# MB_ZBT_memory.net
KiCad netlist of a schematic drawn in Altium Designer
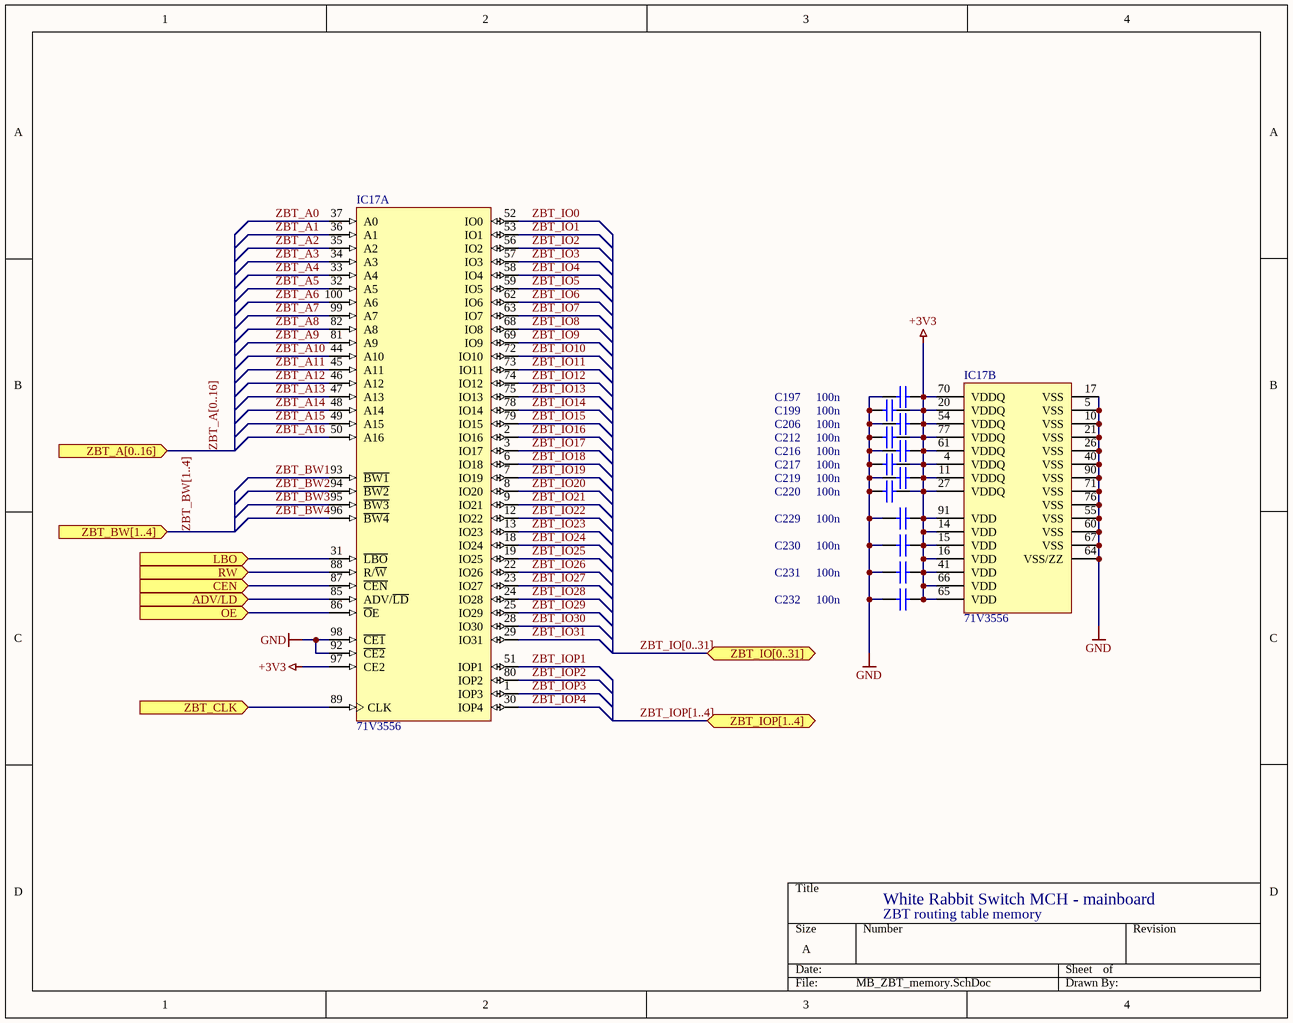
[diagram p0: MB_ZBT_memory.SchDoc]

(export (version "E")
  (design (tool "Eeschema 10.0.6"))
  (components
    (comp (ref "C197")
      (value "100n")
      (footprint "CAPC1005X55N")
      (description "Non-polarised capacitor")
      (fields
        (field (name "PART NUMBER") "CC0402_100NF_16V_10%_X7R")
        (field (name "VOLTAGE") "16V")
        (field (name "AUTHOR") "CERN DEM JLC")
      )
      (libsource (lib "Capacitors") (part "Capacitor - non polarized"))
    )
    (comp (ref "C199")
      (value "100n")
      (footprint "CAPC1005X55N")
      (description "Non-polarised capacitor")
      (fields
        (field (name "PART NUMBER") "CC0402_100NF_16V_10%_X7R")
        (field (name "VOLTAGE") "16V")
        (field (name "AUTHOR") "CERN DEM JLC")
      )
      (libsource (lib "Capacitors") (part "Capacitor - non polarized"))
    )
    (comp (ref "C206")
      (value "100n")
      (footprint "CAPC1005X55N")
      (description "Non-polarised capacitor")
      (fields
        (field (name "PART NUMBER") "CC0402_100NF_16V_10%_X7R")
        (field (name "VOLTAGE") "16V")
        (field (name "AUTHOR") "CERN DEM JLC")
      )
      (libsource (lib "Capacitors") (part "Capacitor - non polarized"))
    )
    (comp (ref "C212")
      (value "100n")
      (footprint "CAPC1005X55N")
      (description "Non-polarised capacitor")
      (fields
        (field (name "PART NUMBER") "CC0402_100NF_16V_10%_X7R")
        (field (name "VOLTAGE") "16V")
        (field (name "AUTHOR") "CERN DEM JLC")
      )
      (libsource (lib "Capacitors") (part "Capacitor - non polarized"))
    )
    (comp (ref "C216")
      (value "100n")
      (footprint "CAPC1005X55N")
      (description "Non-polarised capacitor")
      (fields
        (field (name "PART NUMBER") "CC0402_100NF_16V_10%_X7R")
        (field (name "VOLTAGE") "16V")
        (field (name "AUTHOR") "CERN DEM JLC")
      )
      (libsource (lib "Capacitors") (part "Capacitor - non polarized"))
    )
    (comp (ref "C217")
      (value "100n")
      (footprint "CAPC1005X55N")
      (description "Non-polarised capacitor")
      (fields
        (field (name "PART NUMBER") "CC0402_100NF_16V_10%_X7R")
        (field (name "VOLTAGE") "16V")
        (field (name "AUTHOR") "CERN DEM JLC")
      )
      (libsource (lib "Capacitors") (part "Capacitor - non polarized"))
    )
    (comp (ref "C219")
      (value "100n")
      (footprint "CAPC1005X55N")
      (description "Non-polarised capacitor")
      (fields
        (field (name "PART NUMBER") "CC0402_100NF_16V_10%_X7R")
        (field (name "VOLTAGE") "16V")
        (field (name "AUTHOR") "CERN DEM JLC")
      )
      (libsource (lib "Capacitors") (part "Capacitor - non polarized"))
    )
    (comp (ref "C220")
      (value "100n")
      (footprint "CAPC1005X55N")
      (description "Non-polarised capacitor")
      (fields
        (field (name "PART NUMBER") "CC0402_100NF_16V_10%_X7R")
        (field (name "VOLTAGE") "16V")
        (field (name "AUTHOR") "CERN DEM JLC")
      )
      (libsource (lib "Capacitors") (part "Capacitor - non polarized"))
    )
    (comp (ref "C229")
      (value "100n")
      (footprint "CAPC1005X55N")
      (description "Non-polarised capacitor")
      (fields
        (field (name "PART NUMBER") "CC0402_100NF_16V_10%_X7R")
        (field (name "VOLTAGE") "16V")
        (field (name "AUTHOR") "CERN DEM JLC")
      )
      (libsource (lib "Capacitors") (part "Capacitor - non polarized"))
    )
    (comp (ref "C230")
      (value "100n")
      (footprint "CAPC1005X55N")
      (description "Non-polarised capacitor")
      (fields
        (field (name "PART NUMBER") "CC0402_100NF_16V_10%_X7R")
        (field (name "VOLTAGE") "16V")
        (field (name "AUTHOR") "CERN DEM JLC")
      )
      (libsource (lib "Capacitors") (part "Capacitor - non polarized"))
    )
    (comp (ref "C231")
      (value "100n")
      (footprint "CAPC1005X55N")
      (description "Non-polarised capacitor")
      (fields
        (field (name "PART NUMBER") "CC0402_100NF_16V_10%_X7R")
        (field (name "VOLTAGE") "16V")
        (field (name "AUTHOR") "CERN DEM JLC")
      )
      (libsource (lib "Capacitors") (part "Capacitor - non polarized"))
    )
    (comp (ref "C232")
      (value "100n")
      (footprint "CAPC1005X55N")
      (description "Non-polarised capacitor")
      (fields
        (field (name "PART NUMBER") "CC0402_100NF_16V_10%_X7R")
        (field (name "VOLTAGE") "16V")
        (field (name "AUTHOR") "CERN DEM JLC")
      )
      (libsource (lib "Capacitors") (part "Capacitor - non polarized"))
    )
    (comp (ref "IC17")
      (value "71V3556")
      (footprint "TQFP100A101")
      (description "4.5 Mbit ZBT SRAM")
      (libsource (lib "wr_switch") (part "71V3556"))
    )
  )
  (nets
    (net (code "1") (name "+3V3") (class "Default")
      (node (ref "C197") (pin "2") (pinfunction "2_2") (pintype "passive"))
      (node (ref "C199") (pin "2") (pinfunction "2_2") (pintype "passive"))
      (node (ref "C206") (pin "2") (pinfunction "2_2") (pintype "passive"))
      (node (ref "C212") (pin "2") (pinfunction "2_2") (pintype "passive"))
      (node (ref "C216") (pin "2") (pinfunction "2_2") (pintype "passive"))
      (node (ref "C217") (pin "2") (pinfunction "2_2") (pintype "passive"))
      (node (ref "C219") (pin "2") (pinfunction "2_2") (pintype "passive"))
      (node (ref "C220") (pin "2") (pinfunction "2_2") (pintype "passive"))
      (node (ref "C229") (pin "2") (pinfunction "2_2") (pintype "passive"))
      (node (ref "C230") (pin "2") (pinfunction "2_2") (pintype "passive"))
      (node (ref "C231") (pin "2") (pinfunction "2_2") (pintype "passive"))
      (node (ref "C232") (pin "2") (pinfunction "2_2") (pintype "passive"))
      (node (ref "IC17") (pin "11") (pinfunction "VDDQ_11") (pintype "power_in"))
      (node (ref "IC17") (pin "14") (pinfunction "VDD_14") (pintype "power_in"))
      (node (ref "IC17") (pin "15") (pinfunction "VDD_15") (pintype "power_in"))
      (node (ref "IC17") (pin "16") (pinfunction "VDD_16") (pintype "power_in"))
      (node (ref "IC17") (pin "20") (pinfunction "VDDQ_20") (pintype "power_in"))
      (node (ref "IC17") (pin "27") (pinfunction "VDDQ_27") (pintype "power_in"))
      (node (ref "IC17") (pin "4") (pinfunction "VDDQ_4") (pintype "power_in"))
      (node (ref "IC17") (pin "41") (pinfunction "VDD_41") (pintype "power_in"))
      (node (ref "IC17") (pin "54") (pinfunction "VDDQ_54") (pintype "power_in"))
      (node (ref "IC17") (pin "61") (pinfunction "VDDQ_61") (pintype "power_in"))
      (node (ref "IC17") (pin "65") (pinfunction "VDD_65") (pintype "power_in"))
      (node (ref "IC17") (pin "66") (pinfunction "VDD_66") (pintype "power_in"))
      (node (ref "IC17") (pin "70") (pinfunction "VDDQ_70") (pintype "power_in"))
      (node (ref "IC17") (pin "77") (pinfunction "VDDQ_77") (pintype "power_in"))
      (node (ref "IC17") (pin "91") (pinfunction "VDD_91") (pintype "power_in"))
      (node (ref "IC17") (pin "97") (pinfunction "CE2_97") (pintype "input"))
    )
    (net (code "2") (name "/ADV{slash}LD") (class "Default")
      (node (ref "IC17") (pin "85") (pinfunction "ADV/~{LD}_85") (pintype "input"))
    )
    (net (code "3") (name "/CEN") (class "Default")
      (node (ref "IC17") (pin "87") (pinfunction "~{CEN}_87") (pintype "input"))
    )
    (net (code "4") (name "/LBO") (class "Default")
      (node (ref "IC17") (pin "31") (pinfunction "~{LBO}_31") (pintype "input"))
    )
    (net (code "5") (name "/OE") (class "Default")
      (node (ref "IC17") (pin "86") (pinfunction "~{O}E_86") (pintype "input"))
    )
    (net (code "6") (name "/RW") (class "Default")
      (node (ref "IC17") (pin "88") (pinfunction "R/~{W}_88") (pintype "input"))
    )
    (net (code "7") (name "/ZBT_A0") (class "Default")
      (node (ref "IC17") (pin "37") (pinfunction "A0_37") (pintype "input"))
    )
    (net (code "8") (name "/ZBT_A1") (class "Default")
      (node (ref "IC17") (pin "36") (pinfunction "A1_36") (pintype "input"))
    )
    (net (code "9") (name "/ZBT_A2") (class "Default")
      (node (ref "IC17") (pin "35") (pinfunction "A2_35") (pintype "input"))
    )
    (net (code "10") (name "/ZBT_A3") (class "Default")
      (node (ref "IC17") (pin "34") (pinfunction "A3_34") (pintype "input"))
    )
    (net (code "11") (name "/ZBT_A4") (class "Default")
      (node (ref "IC17") (pin "33") (pinfunction "A4_33") (pintype "input"))
    )
    (net (code "12") (name "/ZBT_A5") (class "Default")
      (node (ref "IC17") (pin "32") (pinfunction "A5_32") (pintype "input"))
    )
    (net (code "13") (name "/ZBT_A6") (class "Default")
      (node (ref "IC17") (pin "100") (pinfunction "A6_100") (pintype "input"))
    )
    (net (code "14") (name "/ZBT_A7") (class "Default")
      (node (ref "IC17") (pin "99") (pinfunction "A7_99") (pintype "input"))
    )
    (net (code "15") (name "/ZBT_A8") (class "Default")
      (node (ref "IC17") (pin "82") (pinfunction "A8_82") (pintype "input"))
    )
    (net (code "16") (name "/ZBT_A9") (class "Default")
      (node (ref "IC17") (pin "81") (pinfunction "A9_81") (pintype "input"))
    )
    (net (code "17") (name "/ZBT_A10") (class "Default")
      (node (ref "IC17") (pin "44") (pinfunction "A10_44") (pintype "input"))
    )
    (net (code "18") (name "/ZBT_A11") (class "Default")
      (node (ref "IC17") (pin "45") (pinfunction "A11_45") (pintype "input"))
    )
    (net (code "19") (name "/ZBT_A12") (class "Default")
      (node (ref "IC17") (pin "46") (pinfunction "A12_46") (pintype "input"))
    )
    (net (code "20") (name "/ZBT_A13") (class "Default")
      (node (ref "IC17") (pin "47") (pinfunction "A13_47") (pintype "input"))
    )
    (net (code "21") (name "/ZBT_A14") (class "Default")
      (node (ref "IC17") (pin "48") (pinfunction "A14_48") (pintype "input"))
    )
    (net (code "22") (name "/ZBT_A15") (class "Default")
      (node (ref "IC17") (pin "49") (pinfunction "A15_49") (pintype "input"))
    )
    (net (code "23") (name "/ZBT_A16") (class "Default")
      (node (ref "IC17") (pin "50") (pinfunction "A16_50") (pintype "input"))
    )
    (net (code "25") (name "/ZBT_BW1") (class "Default")
      (node (ref "IC17") (pin "93") (pinfunction "~{BW1}_93") (pintype "input"))
    )
    (net (code "26") (name "/ZBT_BW2") (class "Default")
      (node (ref "IC17") (pin "94") (pinfunction "~{BW2}_94") (pintype "input"))
    )
    (net (code "27") (name "/ZBT_BW3") (class "Default")
      (node (ref "IC17") (pin "95") (pinfunction "~{BW3}_95") (pintype "input"))
    )
    (net (code "28") (name "/ZBT_BW4") (class "Default")
      (node (ref "IC17") (pin "96") (pinfunction "~{BW4}_96") (pintype "input"))
    )
    (net (code "30") (name "/ZBT_CLK") (class "Default")
      (node (ref "IC17") (pin "89") (pinfunction "CLK_89") (pintype "input"))
    )
    (net (code "31") (name "/ZBT_IO0") (class "Default")
      (node (ref "IC17") (pin "52") (pinfunction "IO0_52") (pintype "bidirectional"))
    )
    (net (code "32") (name "/ZBT_IO1") (class "Default")
      (node (ref "IC17") (pin "53") (pinfunction "IO1_53") (pintype "bidirectional"))
    )
    (net (code "33") (name "/ZBT_IO2") (class "Default")
      (node (ref "IC17") (pin "56") (pinfunction "IO2_56") (pintype "bidirectional"))
    )
    (net (code "34") (name "/ZBT_IO3") (class "Default")
      (node (ref "IC17") (pin "57") (pinfunction "IO3_57") (pintype "bidirectional"))
    )
    (net (code "35") (name "/ZBT_IO4") (class "Default")
      (node (ref "IC17") (pin "58") (pinfunction "IO4_58") (pintype "bidirectional"))
    )
    (net (code "36") (name "/ZBT_IO5") (class "Default")
      (node (ref "IC17") (pin "59") (pinfunction "IO5_59") (pintype "bidirectional"))
    )
    (net (code "37") (name "/ZBT_IO6") (class "Default")
      (node (ref "IC17") (pin "62") (pinfunction "IO6_62") (pintype "bidirectional"))
    )
    (net (code "38") (name "/ZBT_IO7") (class "Default")
      (node (ref "IC17") (pin "63") (pinfunction "IO7_63") (pintype "bidirectional"))
    )
    (net (code "39") (name "/ZBT_IO8") (class "Default")
      (node (ref "IC17") (pin "68") (pinfunction "IO8_68") (pintype "bidirectional"))
    )
    (net (code "40") (name "/ZBT_IO9") (class "Default")
      (node (ref "IC17") (pin "69") (pinfunction "IO9_69") (pintype "bidirectional"))
    )
    (net (code "41") (name "/ZBT_IO10") (class "Default")
      (node (ref "IC17") (pin "72") (pinfunction "IO10_72") (pintype "bidirectional"))
    )
    (net (code "42") (name "/ZBT_IO11") (class "Default")
      (node (ref "IC17") (pin "73") (pinfunction "IO11_73") (pintype "bidirectional"))
    )
    (net (code "43") (name "/ZBT_IO12") (class "Default")
      (node (ref "IC17") (pin "74") (pinfunction "IO12_74") (pintype "bidirectional"))
    )
    (net (code "44") (name "/ZBT_IO13") (class "Default")
      (node (ref "IC17") (pin "75") (pinfunction "IO13_75") (pintype "bidirectional"))
    )
    (net (code "45") (name "/ZBT_IO14") (class "Default")
      (node (ref "IC17") (pin "78") (pinfunction "IO14_78") (pintype "bidirectional"))
    )
    (net (code "46") (name "/ZBT_IO15") (class "Default")
      (node (ref "IC17") (pin "79") (pinfunction "IO15_79") (pintype "bidirectional"))
    )
    (net (code "47") (name "/ZBT_IO16") (class "Default")
      (node (ref "IC17") (pin "2") (pinfunction "IO16_2") (pintype "bidirectional"))
    )
    (net (code "48") (name "/ZBT_IO17") (class "Default")
      (node (ref "IC17") (pin "3") (pinfunction "IO17_3") (pintype "bidirectional"))
    )
    (net (code "49") (name "/ZBT_IO18") (class "Default")
      (node (ref "IC17") (pin "6") (pinfunction "IO18_6") (pintype "bidirectional"))
    )
    (net (code "50") (name "/ZBT_IO19") (class "Default")
      (node (ref "IC17") (pin "7") (pinfunction "IO19_7") (pintype "bidirectional"))
    )
    (net (code "51") (name "/ZBT_IO20") (class "Default")
      (node (ref "IC17") (pin "8") (pinfunction "IO20_8") (pintype "bidirectional"))
    )
    (net (code "52") (name "/ZBT_IO21") (class "Default")
      (node (ref "IC17") (pin "9") (pinfunction "IO21_9") (pintype "bidirectional"))
    )
    (net (code "53") (name "/ZBT_IO22") (class "Default")
      (node (ref "IC17") (pin "12") (pinfunction "IO22_12") (pintype "bidirectional"))
    )
    (net (code "54") (name "/ZBT_IO23") (class "Default")
      (node (ref "IC17") (pin "13") (pinfunction "IO23_13") (pintype "bidirectional"))
    )
    (net (code "55") (name "/ZBT_IO24") (class "Default")
      (node (ref "IC17") (pin "18") (pinfunction "IO24_18") (pintype "bidirectional"))
    )
    (net (code "56") (name "/ZBT_IO25") (class "Default")
      (node (ref "IC17") (pin "19") (pinfunction "IO25_19") (pintype "bidirectional"))
    )
    (net (code "57") (name "/ZBT_IO26") (class "Default")
      (node (ref "IC17") (pin "22") (pinfunction "IO26_22") (pintype "bidirectional"))
    )
    (net (code "58") (name "/ZBT_IO27") (class "Default")
      (node (ref "IC17") (pin "23") (pinfunction "IO27_23") (pintype "bidirectional"))
    )
    (net (code "59") (name "/ZBT_IO28") (class "Default")
      (node (ref "IC17") (pin "24") (pinfunction "IO28_24") (pintype "bidirectional"))
    )
    (net (code "60") (name "/ZBT_IO29") (class "Default")
      (node (ref "IC17") (pin "25") (pinfunction "IO29_25") (pintype "bidirectional"))
    )
    (net (code "61") (name "/ZBT_IO30") (class "Default")
      (node (ref "IC17") (pin "28") (pinfunction "IO30_28") (pintype "bidirectional"))
    )
    (net (code "62") (name "/ZBT_IO31") (class "Default")
      (node (ref "IC17") (pin "29") (pinfunction "IO31_29") (pintype "bidirectional"))
    )
    (net (code "63") (name "/ZBT_IOP1") (class "Default")
      (node (ref "IC17") (pin "51") (pinfunction "IOP1_51") (pintype "bidirectional"))
    )
    (net (code "64") (name "/ZBT_IOP2") (class "Default")
      (node (ref "IC17") (pin "80") (pinfunction "IOP2_80") (pintype "bidirectional"))
    )
    (net (code "65") (name "/ZBT_IOP3") (class "Default")
      (node (ref "IC17") (pin "1") (pinfunction "IOP3_1") (pintype "bidirectional"))
    )
    (net (code "66") (name "/ZBT_IOP4") (class "Default")
      (node (ref "IC17") (pin "30") (pinfunction "IOP4_30") (pintype "bidirectional"))
    )
    (net (code "69") (name "GND") (class "Default")
      (node (ref "C197") (pin "1") (pinfunction "1_1") (pintype "passive"))
      (node (ref "C199") (pin "1") (pinfunction "1_1") (pintype "passive"))
      (node (ref "C206") (pin "1") (pinfunction "1_1") (pintype "passive"))
      (node (ref "C212") (pin "1") (pinfunction "1_1") (pintype "passive"))
      (node (ref "C216") (pin "1") (pinfunction "1_1") (pintype "passive"))
      (node (ref "C217") (pin "1") (pinfunction "1_1") (pintype "passive"))
      (node (ref "C219") (pin "1") (pinfunction "1_1") (pintype "passive"))
      (node (ref "C220") (pin "1") (pinfunction "1_1") (pintype "passive"))
      (node (ref "C229") (pin "1") (pinfunction "1_1") (pintype "passive"))
      (node (ref "C230") (pin "1") (pinfunction "1_1") (pintype "passive"))
      (node (ref "C231") (pin "1") (pinfunction "1_1") (pintype "passive"))
      (node (ref "C232") (pin "1") (pinfunction "1_1") (pintype "passive"))
      (node (ref "IC17") (pin "10") (pinfunction "VSS_10") (pintype "power_in"))
      (node (ref "IC17") (pin "17") (pinfunction "VSS_17") (pintype "power_in"))
      (node (ref "IC17") (pin "21") (pinfunction "VSS_21") (pintype "power_in"))
      (node (ref "IC17") (pin "26") (pinfunction "VSS_26") (pintype "power_in"))
      (node (ref "IC17") (pin "40") (pinfunction "VSS_40") (pintype "power_in"))
      (node (ref "IC17") (pin "5") (pinfunction "VSS_5") (pintype "power_in"))
      (node (ref "IC17") (pin "55") (pinfunction "VSS_55") (pintype "power_in"))
      (node (ref "IC17") (pin "60") (pinfunction "VSS_60") (pintype "power_in"))
      (node (ref "IC17") (pin "64") (pinfunction "VSS/ZZ_64") (pintype "power_in"))
      (node (ref "IC17") (pin "67") (pinfunction "VSS_67") (pintype "power_in"))
      (node (ref "IC17") (pin "71") (pinfunction "VSS_71") (pintype "power_in"))
      (node (ref "IC17") (pin "76") (pinfunction "VSS_76") (pintype "power_in"))
      (node (ref "IC17") (pin "90") (pinfunction "VSS_90") (pintype "power_in"))
      (node (ref "IC17") (pin "92") (pinfunction "~{CE2}_92") (pintype "input"))
      (node (ref "IC17") (pin "98") (pinfunction "~{CE1}_98") (pintype "input"))
    )
  )
)
